# Gigabit_Ethernet.net
KiCad netlist of a schematic drawn in Altium Designer
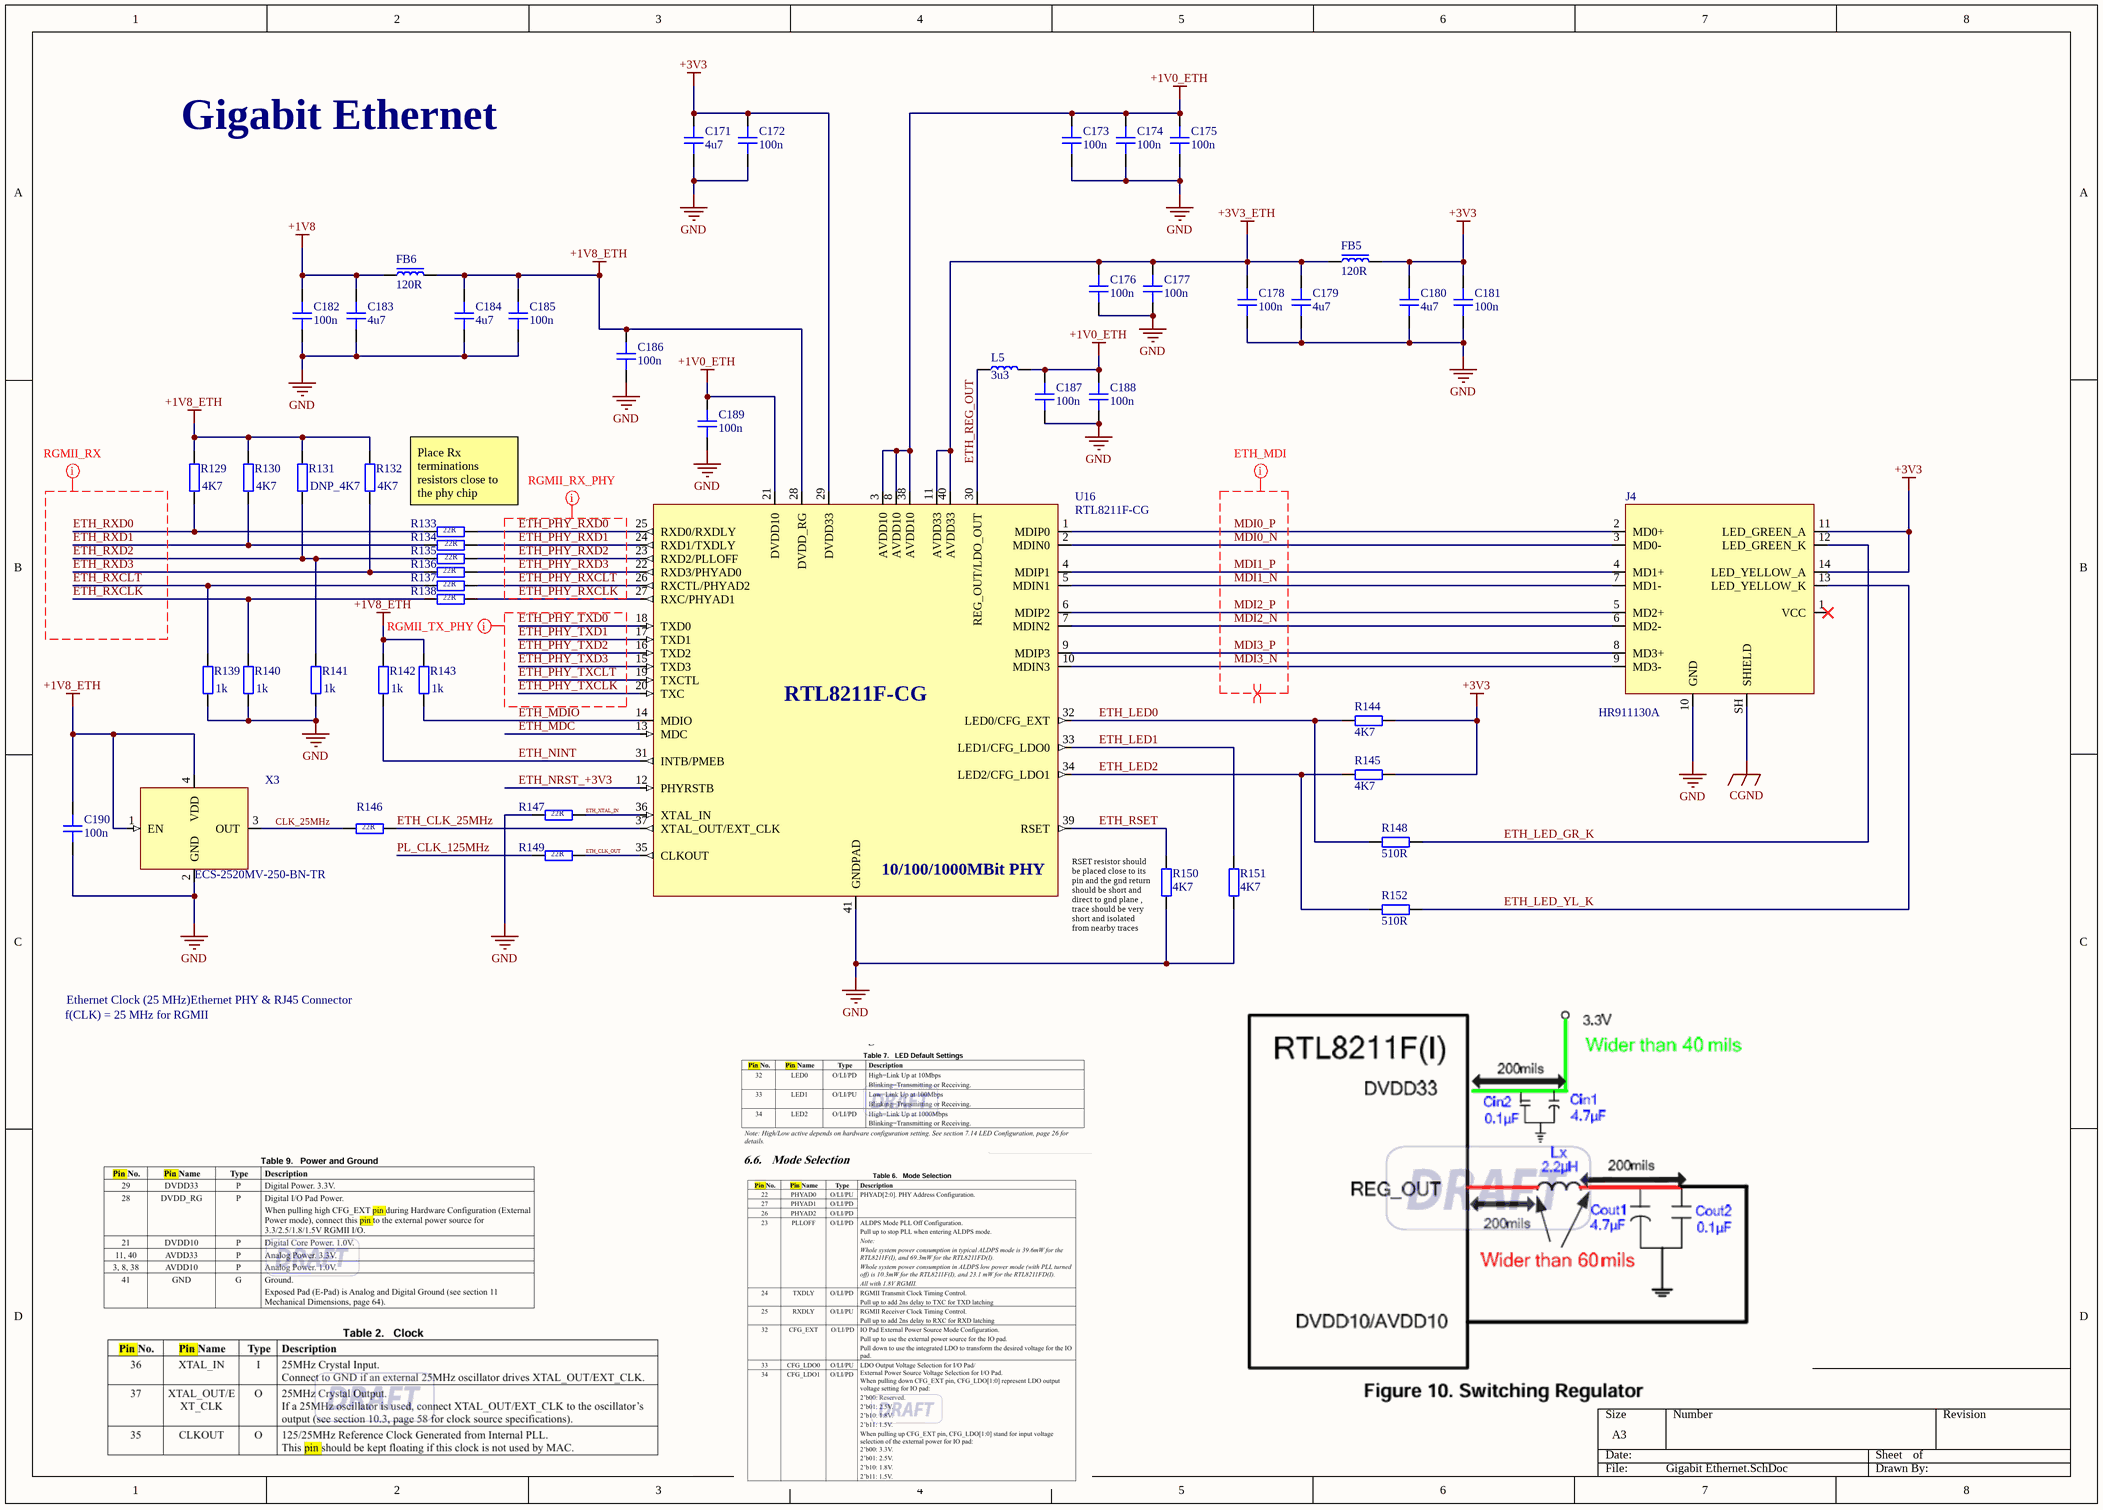
[diagram p0: Gigabit Ethernet.SchDoc]

(export (version "E")
  (design (tool "Eeschema 10.0.6"))
  (components
    (comp (ref "C171")
      (value "4u7")
      (footprint "CAP_0402")
      (description "Capacitor SMD 0402")
      (libsource (lib "Schematic-Lib-PhilsLab") (part "CAP_0402"))
    )
    (comp (ref "C172")
      (value "100n")
      (footprint "CAP_0402")
      (description "Capacitor SMD 0402")
      (libsource (lib "Schematic-Lib-PhilsLab") (part "CAP_0402"))
    )
    (comp (ref "C173")
      (value "100n")
      (footprint "CAP_0402")
      (description "Capacitor SMD 0402")
      (libsource (lib "Schematic-Lib-PhilsLab") (part "CAP_0402"))
    )
    (comp (ref "C174")
      (value "100n")
      (footprint "CAP_0402")
      (description "Capacitor SMD 0402")
      (libsource (lib "Schematic-Lib-PhilsLab") (part "CAP_0402"))
    )
    (comp (ref "C175")
      (value "100n")
      (footprint "CAP_0402")
      (description "Capacitor SMD 0402")
      (libsource (lib "Schematic-Lib-PhilsLab") (part "CAP_0402"))
    )
    (comp (ref "C176")
      (value "100n")
      (footprint "CAP_0402")
      (description "Capacitor SMD 0402")
      (libsource (lib "Schematic-Lib-PhilsLab") (part "CAP_0402"))
    )
    (comp (ref "C177")
      (value "100n")
      (footprint "CAP_0402")
      (description "Capacitor SMD 0402")
      (libsource (lib "Schematic-Lib-PhilsLab") (part "CAP_0402"))
    )
    (comp (ref "C178")
      (value "100n")
      (footprint "CAP_0402")
      (description "Capacitor SMD 0402")
      (libsource (lib "Schematic-Lib-PhilsLab") (part "CAP_0402"))
    )
    (comp (ref "C179")
      (value "4u7")
      (footprint "CAP_0402")
      (description "Capacitor SMD 0402")
      (libsource (lib "Schematic-Lib-PhilsLab") (part "CAP_0402"))
    )
    (comp (ref "C180")
      (value "4u7")
      (footprint "CAP_0402")
      (description "Capacitor SMD 0402")
      (libsource (lib "Schematic-Lib-PhilsLab") (part "CAP_0402"))
    )
    (comp (ref "C181")
      (value "100n")
      (footprint "CAP_0402")
      (description "Capacitor SMD 0402")
      (libsource (lib "Schematic-Lib-PhilsLab") (part "CAP_0402"))
    )
    (comp (ref "C182")
      (value "100n")
      (footprint "CAP_0402")
      (description "Capacitor SMD 0402")
      (libsource (lib "Schematic-Lib-PhilsLab") (part "CAP_0402"))
    )
    (comp (ref "C183")
      (value "4u7")
      (footprint "CAP_0402")
      (description "Capacitor SMD 0402")
      (libsource (lib "Schematic-Lib-PhilsLab") (part "CAP_0402"))
    )
    (comp (ref "C184")
      (value "4u7")
      (footprint "CAP_0402")
      (description "Capacitor SMD 0402")
      (libsource (lib "Schematic-Lib-PhilsLab") (part "CAP_0402"))
    )
    (comp (ref "C185")
      (value "100n")
      (footprint "CAP_0402")
      (description "Capacitor SMD 0402")
      (libsource (lib "Schematic-Lib-PhilsLab") (part "CAP_0402"))
    )
    (comp (ref "C186")
      (value "100n")
      (footprint "CAP_0402")
      (description "Capacitor SMD 0402")
      (libsource (lib "Schematic-Lib-PhilsLab") (part "CAP_0402"))
    )
    (comp (ref "C187")
      (value "100n")
      (footprint "CAP_0402")
      (description "Capacitor SMD 0402")
      (libsource (lib "Schematic-Lib-PhilsLab") (part "CAP_0402"))
    )
    (comp (ref "C188")
      (value "100n")
      (footprint "CAP_0402")
      (description "Capacitor SMD 0402")
      (libsource (lib "Schematic-Lib-PhilsLab") (part "CAP_0402"))
    )
    (comp (ref "C189")
      (value "100n")
      (footprint "CAP_0402")
      (description "Capacitor SMD 0402")
      (libsource (lib "Schematic-Lib-PhilsLab") (part "CAP_0402"))
    )
    (comp (ref "C190")
      (value "100n")
      (footprint "CAP_0402")
      (description "Capacitor SMD 0402")
      (libsource (lib "Schematic-Lib-PhilsLab") (part "CAP_0402"))
    )
    (comp (ref "FB5")
      (value "120R")
      (footprint "FB_0402")
      (description "Ferrite Bead SMD 0402")
      (libsource (lib "") (part "FB_0402_1"))
    )
    (comp (ref "FB6")
      (value "120R")
      (footprint "FB_0402")
      (description "Ferrite Bead SMD 0402")
      (libsource (lib "Schematic-Lib-PhilsLab") (part "FB_0402"))
    )
    (comp (ref "J4")
      (value "HR911130A")
      (footprint "HR911130A")
      (description "100/1000Base-T Magnetics Single-Port RJ45 Connector with Integrated Magnetics and LEDs")
      (fields (field (name "MANUFACTURER") "Hanrun"))
      (libsource (lib "Schematic-Lib-PhilsLab") (part "HR911130A"))
    )
    (comp (ref "L5")
      (value "3u3")
      (footprint "IND_0402")
      (description "Inductor SMD 0402")
      (fields (field (name "Comment") "L0402"))
      (libsource (lib "Schematic-Lib-PhilsLab") (part "IND_0402"))
    )
    (comp (ref "R129")
      (value "4K7")
      (footprint "RES_0402")
      (description "Resistor SMD 0402")
      (fields (field (name "Comment") "R0402"))
      (libsource (lib "Schematic-Lib-PhilsLab") (part "RES_0402"))
    )
    (comp (ref "R130")
      (value "4K7")
      (footprint "RES_0402")
      (description "Resistor SMD 0402")
      (fields (field (name "Comment") "R0402"))
      (libsource (lib "Schematic-Lib-PhilsLab") (part "RES_0402"))
    )
    (comp (ref "R131")
      (value "DNP_4K7")
      (footprint "RES_0402")
      (description "Resistor SMD 0402")
      (fields (field (name "Comment") "R0402"))
      (libsource (lib "Schematic-Lib-PhilsLab") (part "RES_0402"))
    )
    (comp (ref "R132")
      (value "4K7")
      (footprint "RES_0402")
      (description "Resistor SMD 0402")
      (fields (field (name "Comment") "R0402"))
      (libsource (lib "Schematic-Lib-PhilsLab") (part "RES_0402"))
    )
    (comp (ref "R133")
      (value "22R")
      (footprint "RES_0402")
      (description "Resistor SMD 0402")
      (fields (field (name "Comment") "R0402"))
      (libsource (lib "Schematic-Lib-PhilsLab") (part "RES_0402"))
    )
    (comp (ref "R134")
      (value "22R")
      (footprint "RES_0402")
      (description "Resistor SMD 0402")
      (fields (field (name "Comment") "R0402"))
      (libsource (lib "Schematic-Lib-PhilsLab") (part "RES_0402"))
    )
    (comp (ref "R135")
      (value "22R")
      (footprint "RES_0402")
      (description "Resistor SMD 0402")
      (fields (field (name "Comment") "R0402"))
      (libsource (lib "Schematic-Lib-PhilsLab") (part "RES_0402"))
    )
    (comp (ref "R136")
      (value "22R")
      (footprint "RES_0402")
      (description "Resistor SMD 0402")
      (fields (field (name "Comment") "R0402"))
      (libsource (lib "Schematic-Lib-PhilsLab") (part "RES_0402"))
    )
    (comp (ref "R137")
      (value "22R")
      (footprint "RES_0402")
      (description "Resistor SMD 0402")
      (fields (field (name "Comment") "R0402"))
      (libsource (lib "Schematic-Lib-PhilsLab") (part "RES_0402"))
    )
    (comp (ref "R138")
      (value "22R")
      (footprint "RES_0402")
      (description "Resistor SMD 0402")
      (fields (field (name "Comment") "R0402"))
      (libsource (lib "Schematic-Lib-PhilsLab") (part "RES_0402"))
    )
    (comp (ref "R139")
      (value "1k")
      (footprint "RES_0402")
      (description "Resistor SMD 0402")
      (fields (field (name "Comment") "R0402"))
      (libsource (lib "Schematic-Lib-PhilsLab") (part "RES_0402"))
    )
    (comp (ref "R140")
      (value "1k")
      (footprint "RES_0402")
      (description "Resistor SMD 0402")
      (fields (field (name "Comment") "R0402"))
      (libsource (lib "Schematic-Lib-PhilsLab") (part "RES_0402"))
    )
    (comp (ref "R141")
      (value "1k")
      (footprint "RES_0402")
      (description "Resistor SMD 0402")
      (fields (field (name "Comment") "R0402"))
      (libsource (lib "Schematic-Lib-PhilsLab") (part "RES_0402"))
    )
    (comp (ref "R142")
      (value "1k")
      (footprint "RES_0402")
      (description "Resistor SMD 0402")
      (fields (field (name "Comment") "R0402"))
      (libsource (lib "Schematic-Lib-PhilsLab") (part "RES_0402"))
    )
    (comp (ref "R143")
      (value "1k")
      (footprint "RES_0402")
      (description "Resistor SMD 0402")
      (fields (field (name "Comment") "R0402"))
      (libsource (lib "Schematic-Lib-PhilsLab") (part "RES_0402"))
    )
    (comp (ref "R144")
      (value "4K7")
      (footprint "RES_0402")
      (description "Resistor SMD 0402")
      (fields (field (name "Comment") "R0402"))
      (libsource (lib "Schematic-Lib-PhilsLab") (part "RES_0402"))
    )
    (comp (ref "R145")
      (value "4K7")
      (footprint "RES_0402")
      (description "Resistor SMD 0402")
      (fields (field (name "Comment") "R0402"))
      (libsource (lib "Schematic-Lib-PhilsLab") (part "RES_0402"))
    )
    (comp (ref "R146")
      (value "22R")
      (footprint "RES_0402")
      (description "Resistor SMD 0402")
      (fields (field (name "Comment") "R0402"))
      (libsource (lib "Schematic-Lib-PhilsLab") (part "RES_0402"))
    )
    (comp (ref "R147")
      (value "22R")
      (footprint "RES_0402")
      (description "Resistor SMD 0402")
      (fields (field (name "Comment") "R0402"))
      (libsource (lib "Schematic-Lib-PhilsLab") (part "RES_0402"))
    )
    (comp (ref "R148")
      (value "510R")
      (footprint "RES_0402")
      (description "Resistor SMD 0402")
      (fields (field (name "Comment") "R0402"))
      (libsource (lib "Schematic-Lib-PhilsLab") (part "RES_0402"))
    )
    (comp (ref "R149")
      (value "22R")
      (footprint "RES_0402")
      (description "Resistor SMD 0402")
      (fields (field (name "Comment") "R0402"))
      (libsource (lib "Schematic-Lib-PhilsLab") (part "RES_0402"))
    )
    (comp (ref "R150")
      (value "4K7")
      (footprint "RES_0402")
      (description "Resistor SMD 0402")
      (fields (field (name "Comment") "R0402"))
      (libsource (lib "Schematic-Lib-PhilsLab") (part "RES_0402"))
    )
    (comp (ref "R151")
      (value "4K7")
      (footprint "RES_0402")
      (description "Resistor SMD 0402")
      (fields (field (name "Comment") "R0402"))
      (libsource (lib "Schematic-Lib-PhilsLab") (part "RES_0402"))
    )
    (comp (ref "R152")
      (value "510R")
      (footprint "RES_0402")
      (description "Resistor SMD 0402")
      (fields (field (name "Comment") "R0402"))
      (libsource (lib "Schematic-Lib-PhilsLab") (part "RES_0402"))
    )
    (comp (ref "U16")
      (value "RTL8211F-CG")
      (footprint "QFN-40-0.4-EP")
      (description "INTEGRATED 10/100/1000M ETHERNET PRECISION TRANSCEIVER")
      (fields (field (name "MANUFACTURER") "Realtek"))
      (libsource (lib "Schematic-Lib-PhilsLab") (part "RTL8211F-CG"))
    )
    (comp (ref "X3")
      (value "ECS-2520MV-250-BN-TR")
      (footprint "XTAL_2520")
      (fields
        (field (name "MANUFACTURER") "ECS")
        (field (name "MANUFACTURER PART NUMBER") "ECS-2520MV-130-BN-TR")
      )
      (libsource (lib "Schematic-Lib-PhilsLab") (part "ECS-2520MV-130-BN-TR"))
    )
  )
  (nets
    (net (code "1") (name "+1V0_ETH") (class "Default")
      (node (ref "C173") (pin "2") (pinfunction "2_2") (pintype "passive"))
      (node (ref "C174") (pin "2") (pinfunction "2_2") (pintype "passive"))
      (node (ref "C175") (pin "2") (pinfunction "2_2") (pintype "passive"))
      (node (ref "C187") (pin "2") (pinfunction "2_2") (pintype "passive"))
      (node (ref "C188") (pin "2") (pinfunction "2_2") (pintype "passive"))
      (node (ref "C189") (pin "2") (pinfunction "2_2") (pintype "passive"))
      (node (ref "L5") (pin "2") (pinfunction "2_2") (pintype "passive"))
      (node (ref "U16") (pin "21") (pinfunction "DVDD10_21") (pintype "power_in"))
      (node (ref "U16") (pin "3") (pinfunction "AVDD10_3") (pintype "power_in"))
      (node (ref "U16") (pin "38") (pinfunction "AVDD10_38") (pintype "power_in"))
      (node (ref "U16") (pin "8") (pinfunction "AVDD10_8") (pintype "power_in"))
    )
    (net (code "2") (name "+1V8") (class "Default")
      (node (ref "C182") (pin "2") (pinfunction "2_2") (pintype "passive"))
      (node (ref "C183") (pin "2") (pinfunction "2_2") (pintype "passive"))
      (node (ref "FB6") (pin "1") (pinfunction "1_1") (pintype "passive"))
    )
    (net (code "3") (name "+1V8_ETH") (class "Default")
      (node (ref "C184") (pin "2") (pinfunction "2_2") (pintype "passive"))
      (node (ref "C185") (pin "2") (pinfunction "2_2") (pintype "passive"))
      (node (ref "C186") (pin "2") (pinfunction "2_2") (pintype "passive"))
      (node (ref "C190") (pin "2") (pinfunction "2_2") (pintype "passive"))
      (node (ref "FB6") (pin "2") (pinfunction "2_2") (pintype "passive"))
      (node (ref "R129") (pin "2") (pinfunction "2_2") (pintype "passive"))
      (node (ref "R130") (pin "2") (pinfunction "2_2") (pintype "passive"))
      (node (ref "R131") (pin "2") (pinfunction "2_2") (pintype "passive"))
      (node (ref "R132") (pin "2") (pinfunction "2_2") (pintype "passive"))
      (node (ref "R142") (pin "2") (pinfunction "2_2") (pintype "passive"))
      (node (ref "R143") (pin "2") (pinfunction "2_2") (pintype "passive"))
      (node (ref "U16") (pin "28") (pinfunction "DVDD_RG_28") (pintype "power_in"))
      (node (ref "X3") (pin "1") (pinfunction "EN_1") (pintype "input"))
      (node (ref "X3") (pin "4") (pinfunction "VDD_4") (pintype "power_in"))
    )
    (net (code "4") (name "+3V3") (class "Default")
      (node (ref "C171") (pin "2") (pinfunction "2_2") (pintype "passive"))
      (node (ref "C172") (pin "2") (pinfunction "2_2") (pintype "passive"))
      (node (ref "C180") (pin "2") (pinfunction "2_2") (pintype "passive"))
      (node (ref "C181") (pin "2") (pinfunction "2_2") (pintype "passive"))
      (node (ref "FB5") (pin "1") (pinfunction "1_1") (pintype "passive"))
      (node (ref "J4") (pin "11") (pinfunction "LED_GREEN_A_11") (pintype "passive"))
      (node (ref "J4") (pin "14") (pinfunction "LED_YELLOW_A_14") (pintype "passive"))
      (node (ref "R144") (pin "1") (pinfunction "1_1") (pintype "passive"))
      (node (ref "R145") (pin "1") (pinfunction "1_1") (pintype "passive"))
      (node (ref "U16") (pin "29") (pinfunction "DVDD33_29") (pintype "power_in"))
    )
    (net (code "5") (name "+3V3_ETH") (class "Default")
      (node (ref "C176") (pin "2") (pinfunction "2_2") (pintype "passive"))
      (node (ref "C177") (pin "2") (pinfunction "2_2") (pintype "passive"))
      (node (ref "C178") (pin "2") (pinfunction "2_2") (pintype "passive"))
      (node (ref "C179") (pin "2") (pinfunction "2_2") (pintype "passive"))
      (node (ref "FB5") (pin "2") (pinfunction "2_2") (pintype "passive"))
      (node (ref "U16") (pin "11") (pinfunction "AVDD33_11") (pintype "power_in"))
      (node (ref "U16") (pin "40") (pinfunction "AVDD33_40") (pintype "power_in"))
    )
    (net (code "6") (name "/CLK_25MHz") (class "Default")
      (node (ref "R146") (pin "2") (pinfunction "2_2") (pintype "passive"))
      (node (ref "X3") (pin "3") (pinfunction "OUT_3") (pintype "passive"))
    )
    (net (code "7") (name "/ETH_CLK_25MHz") (class "Default")
      (node (ref "R146") (pin "1") (pinfunction "1_1") (pintype "passive"))
      (node (ref "U16") (pin "37") (pinfunction "XTAL_OUT/EXT_CLK_37") (pintype "output"))
    )
    (net (code "8") (name "/ETH_CLK_OUT") (class "Default")
      (node (ref "R149") (pin "1") (pinfunction "1_1") (pintype "passive"))
      (node (ref "U16") (pin "35") (pinfunction "CLKOUT_35") (pintype "output"))
    )
    (net (code "9") (name "/ETH_LED0") (class "Default")
      (node (ref "R144") (pin "2") (pinfunction "2_2") (pintype "passive"))
      (node (ref "R148") (pin "2") (pinfunction "2_2") (pintype "passive"))
      (node (ref "U16") (pin "32") (pinfunction "LED0/CFG_EXT_32") (pintype "output"))
    )
    (net (code "10") (name "/ETH_LED1") (class "Default")
      (node (ref "R151") (pin "1") (pinfunction "1_1") (pintype "passive"))
      (node (ref "U16") (pin "33") (pinfunction "LED1/CFG_LDO0_33") (pintype "output"))
    )
    (net (code "11") (name "/ETH_LED2") (class "Default")
      (node (ref "R145") (pin "2") (pinfunction "2_2") (pintype "passive"))
      (node (ref "R152") (pin "2") (pinfunction "2_2") (pintype "passive"))
      (node (ref "U16") (pin "34") (pinfunction "LED2/CFG_LDO1_34") (pintype "output"))
    )
    (net (code "12") (name "/ETH_LED_GR_K") (class "Default")
      (node (ref "J4") (pin "12") (pinfunction "LED_GREEN_K_12") (pintype "passive"))
      (node (ref "R148") (pin "1") (pinfunction "1_1") (pintype "passive"))
    )
    (net (code "13") (name "/ETH_LED_YL_K") (class "Default")
      (node (ref "J4") (pin "13") (pinfunction "LED_YELLOW_K_13") (pintype "passive"))
      (node (ref "R152") (pin "1") (pinfunction "1_1") (pintype "passive"))
    )
    (net (code "14") (name "/ETH_MDC") (class "Default")
      (node (ref "U16") (pin "13") (pinfunction "MDC_13") (pintype "input"))
    )
    (net (code "15") (name "/ETH_MDIO") (class "Default")
      (node (ref "R143") (pin "1") (pinfunction "1_1") (pintype "passive"))
      (node (ref "U16") (pin "14") (pinfunction "MDIO_14") (pintype "bidirectional"))
    )
    (net (code "16") (name "/ETH_NINT") (class "Default")
      (node (ref "R142") (pin "1") (pinfunction "1_1") (pintype "passive"))
      (node (ref "U16") (pin "31") (pinfunction "INTB/PMEB_31") (pintype "output"))
    )
    (net (code "17") (name "/ETH_NRST_+3V3") (class "Default")
      (node (ref "U16") (pin "12") (pinfunction "PHYRSTB_12") (pintype "input"))
    )
    (net (code "18") (name "/ETH_PHY_RXCLK") (class "Default")
      (node (ref "R138") (pin "1") (pinfunction "1_1") (pintype "passive"))
      (node (ref "U16") (pin "27") (pinfunction "RXC/PHYAD1_27") (pintype "output"))
    )
    (net (code "19") (name "/ETH_PHY_RXCLT") (class "Default")
      (node (ref "R137") (pin "1") (pinfunction "1_1") (pintype "passive"))
      (node (ref "U16") (pin "26") (pinfunction "RXCTL/PHYAD2_26") (pintype "output"))
    )
    (net (code "20") (name "/ETH_PHY_RXD0") (class "Default")
      (node (ref "R133") (pin "1") (pinfunction "1_1") (pintype "passive"))
      (node (ref "U16") (pin "25") (pinfunction "RXD0/RXDLY_25") (pintype "output"))
    )
    (net (code "21") (name "/ETH_PHY_RXD1") (class "Default")
      (node (ref "R134") (pin "1") (pinfunction "1_1") (pintype "passive"))
      (node (ref "U16") (pin "24") (pinfunction "RXD1/TXDLY_24") (pintype "output"))
    )
    (net (code "22") (name "/ETH_PHY_RXD2") (class "Default")
      (node (ref "R135") (pin "1") (pinfunction "1_1") (pintype "passive"))
      (node (ref "U16") (pin "23") (pinfunction "RXD2/PLLOFF_23") (pintype "output"))
    )
    (net (code "23") (name "/ETH_PHY_RXD3") (class "Default")
      (node (ref "R136") (pin "1") (pinfunction "1_1") (pintype "passive"))
      (node (ref "U16") (pin "22") (pinfunction "RXD3/PHYAD0_22") (pintype "output"))
    )
    (net (code "24") (name "/ETH_PHY_TXCLK") (class "Default")
      (node (ref "U16") (pin "20") (pinfunction "TXC_20") (pintype "input"))
    )
    (net (code "25") (name "/ETH_PHY_TXCLT") (class "Default")
      (node (ref "U16") (pin "19") (pinfunction "TXCTL_19") (pintype "input"))
    )
    (net (code "26") (name "/ETH_PHY_TXD0") (class "Default")
      (node (ref "U16") (pin "18") (pinfunction "TXD0_18") (pintype "input"))
    )
    (net (code "27") (name "/ETH_PHY_TXD1") (class "Default")
      (node (ref "U16") (pin "17") (pinfunction "TXD1_17") (pintype "input"))
    )
    (net (code "28") (name "/ETH_PHY_TXD2") (class "Default")
      (node (ref "U16") (pin "16") (pinfunction "TXD2_16") (pintype "input"))
    )
    (net (code "29") (name "/ETH_PHY_TXD3") (class "Default")
      (node (ref "U16") (pin "15") (pinfunction "TXD3_15") (pintype "input"))
    )
    (net (code "30") (name "/ETH_REG_OUT") (class "Default")
      (node (ref "L5") (pin "1") (pinfunction "1_1") (pintype "passive"))
      (node (ref "U16") (pin "30") (pinfunction "REG_OUT/LDO_OUT_30") (pintype "power_in"))
    )
    (net (code "31") (name "/ETH_RSET") (class "Default")
      (node (ref "R150") (pin "1") (pinfunction "1_1") (pintype "passive"))
      (node (ref "U16") (pin "39") (pinfunction "RSET_39") (pintype "output"))
    )
    (net (code "32") (name "/ETH_RXCLK") (class "Default")
      (node (ref "R138") (pin "2") (pinfunction "2_2") (pintype "passive"))
      (node (ref "R140") (pin "2") (pinfunction "2_2") (pintype "passive"))
    )
    (net (code "33") (name "/ETH_RXCLT") (class "Default")
      (node (ref "R137") (pin "2") (pinfunction "2_2") (pintype "passive"))
      (node (ref "R139") (pin "2") (pinfunction "2_2") (pintype "passive"))
    )
    (net (code "34") (name "/ETH_RXD0") (class "Default")
      (node (ref "R129") (pin "1") (pinfunction "1_1") (pintype "passive"))
      (node (ref "R133") (pin "2") (pinfunction "2_2") (pintype "passive"))
    )
    (net (code "35") (name "/ETH_RXD1") (class "Default")
      (node (ref "R130") (pin "1") (pinfunction "1_1") (pintype "passive"))
      (node (ref "R134") (pin "2") (pinfunction "2_2") (pintype "passive"))
    )
    (net (code "36") (name "/ETH_RXD2") (class "Default")
      (node (ref "R131") (pin "1") (pinfunction "1_1") (pintype "passive"))
      (node (ref "R135") (pin "2") (pinfunction "2_2") (pintype "passive"))
      (node (ref "R141") (pin "2") (pinfunction "2_2") (pintype "passive"))
    )
    (net (code "37") (name "/ETH_RXD3") (class "Default")
      (node (ref "R132") (pin "1") (pinfunction "1_1") (pintype "passive"))
      (node (ref "R136") (pin "2") (pinfunction "2_2") (pintype "passive"))
    )
    (net (code "38") (name "/ETH_XTAL_IN") (class "Default")
      (node (ref "R147") (pin "1") (pinfunction "1_1") (pintype "passive"))
      (node (ref "U16") (pin "36") (pinfunction "XTAL_IN_36") (pintype "input"))
    )
    (net (code "39") (name "/MDI0_N") (class "Default")
      (node (ref "J4") (pin "3") (pinfunction "MD0-_3") (pintype "passive"))
      (node (ref "U16") (pin "2") (pinfunction "MDIN0_2") (pintype "bidirectional"))
    )
    (net (code "40") (name "/MDI0_P") (class "Default")
      (node (ref "J4") (pin "2") (pinfunction "MD0+_2") (pintype "passive"))
      (node (ref "U16") (pin "1") (pinfunction "MDIP0_1") (pintype "bidirectional"))
    )
    (net (code "41") (name "/MDI1_N") (class "Default")
      (node (ref "J4") (pin "7") (pinfunction "MD1-_7") (pintype "passive"))
      (node (ref "U16") (pin "5") (pinfunction "MDIN1_5") (pintype "bidirectional"))
    )
    (net (code "42") (name "/MDI1_P") (class "Default")
      (node (ref "J4") (pin "4") (pinfunction "MD1+_4") (pintype "passive"))
      (node (ref "U16") (pin "4") (pinfunction "MDIP1_4") (pintype "bidirectional"))
    )
    (net (code "43") (name "/MDI2_N") (class "Default")
      (node (ref "J4") (pin "6") (pinfunction "MD2-_6") (pintype "passive"))
      (node (ref "U16") (pin "7") (pinfunction "MDIN2_7") (pintype "bidirectional"))
    )
    (net (code "44") (name "/MDI2_P") (class "Default")
      (node (ref "J4") (pin "5") (pinfunction "MD2+_5") (pintype "passive"))
      (node (ref "U16") (pin "6") (pinfunction "MDIP2_6") (pintype "bidirectional"))
    )
    (net (code "45") (name "/MDI3_N") (class "Default")
      (node (ref "J4") (pin "9") (pinfunction "MD3-_9") (pintype "passive"))
      (node (ref "U16") (pin "10") (pinfunction "MDIN3_10") (pintype "bidirectional"))
    )
    (net (code "46") (name "/MDI3_P") (class "Default")
      (node (ref "J4") (pin "8") (pinfunction "MD3+_8") (pintype "passive"))
      (node (ref "U16") (pin "9") (pinfunction "MDIP3_9") (pintype "bidirectional"))
    )
    (net (code "47") (name "/PL_CLK_125MHz") (class "Default")
      (node (ref "R149") (pin "2") (pinfunction "2_2") (pintype "passive"))
    )
    (net (code "48") (name "CGND") (class "Default")
      (node (ref "J4") (pin "SH") (pinfunction "SHIELD_SH") (pintype "passive"))
    )
    (net (code "49") (name "GND") (class "Default")
      (node (ref "C171") (pin "1") (pinfunction "1_1") (pintype "passive"))
      (node (ref "C172") (pin "1") (pinfunction "1_1") (pintype "passive"))
      (node (ref "C173") (pin "1") (pinfunction "1_1") (pintype "passive"))
      (node (ref "C174") (pin "1") (pinfunction "1_1") (pintype "passive"))
      (node (ref "C175") (pin "1") (pinfunction "1_1") (pintype "passive"))
      (node (ref "C176") (pin "1") (pinfunction "1_1") (pintype "passive"))
      (node (ref "C177") (pin "1") (pinfunction "1_1") (pintype "passive"))
      (node (ref "C178") (pin "1") (pinfunction "1_1") (pintype "passive"))
      (node (ref "C179") (pin "1") (pinfunction "1_1") (pintype "passive"))
      (node (ref "C180") (pin "1") (pinfunction "1_1") (pintype "passive"))
      (node (ref "C181") (pin "1") (pinfunction "1_1") (pintype "passive"))
      (node (ref "C182") (pin "1") (pinfunction "1_1") (pintype "passive"))
      (node (ref "C183") (pin "1") (pinfunction "1_1") (pintype "passive"))
      (node (ref "C184") (pin "1") (pinfunction "1_1") (pintype "passive"))
      (node (ref "C185") (pin "1") (pinfunction "1_1") (pintype "passive"))
      (node (ref "C186") (pin "1") (pinfunction "1_1") (pintype "passive"))
      (node (ref "C187") (pin "1") (pinfunction "1_1") (pintype "passive"))
      (node (ref "C188") (pin "1") (pinfunction "1_1") (pintype "passive"))
      (node (ref "C189") (pin "1") (pinfunction "1_1") (pintype "passive"))
      (node (ref "C190") (pin "1") (pinfunction "1_1") (pintype "passive"))
      (node (ref "J4") (pin "10") (pinfunction "GND_10") (pintype "passive"))
      (node (ref "R139") (pin "1") (pinfunction "1_1") (pintype "passive"))
      (node (ref "R140") (pin "1") (pinfunction "1_1") (pintype "passive"))
      (node (ref "R141") (pin "1") (pinfunction "1_1") (pintype "passive"))
      (node (ref "R147") (pin "2") (pinfunction "2_2") (pintype "passive"))
      (node (ref "R150") (pin "2") (pinfunction "2_2") (pintype "passive"))
      (node (ref "R151") (pin "2") (pinfunction "2_2") (pintype "passive"))
      (node (ref "U16") (pin "41") (pinfunction "GNDPAD_41") (pintype "power_in"))
      (node (ref "X3") (pin "2") (pinfunction "GND_2") (pintype "power_in"))
    )
    (net (code "50") (name "unconnected-(J4-VCC-Pad1)") (class "Default")
      (node (ref "J4") (pin "1") (pinfunction "VCC_1") (pintype "passive+no_connect"))
    )
  )
)
